# femto.net
KiCad netlist of a schematic drawn in EAGLE
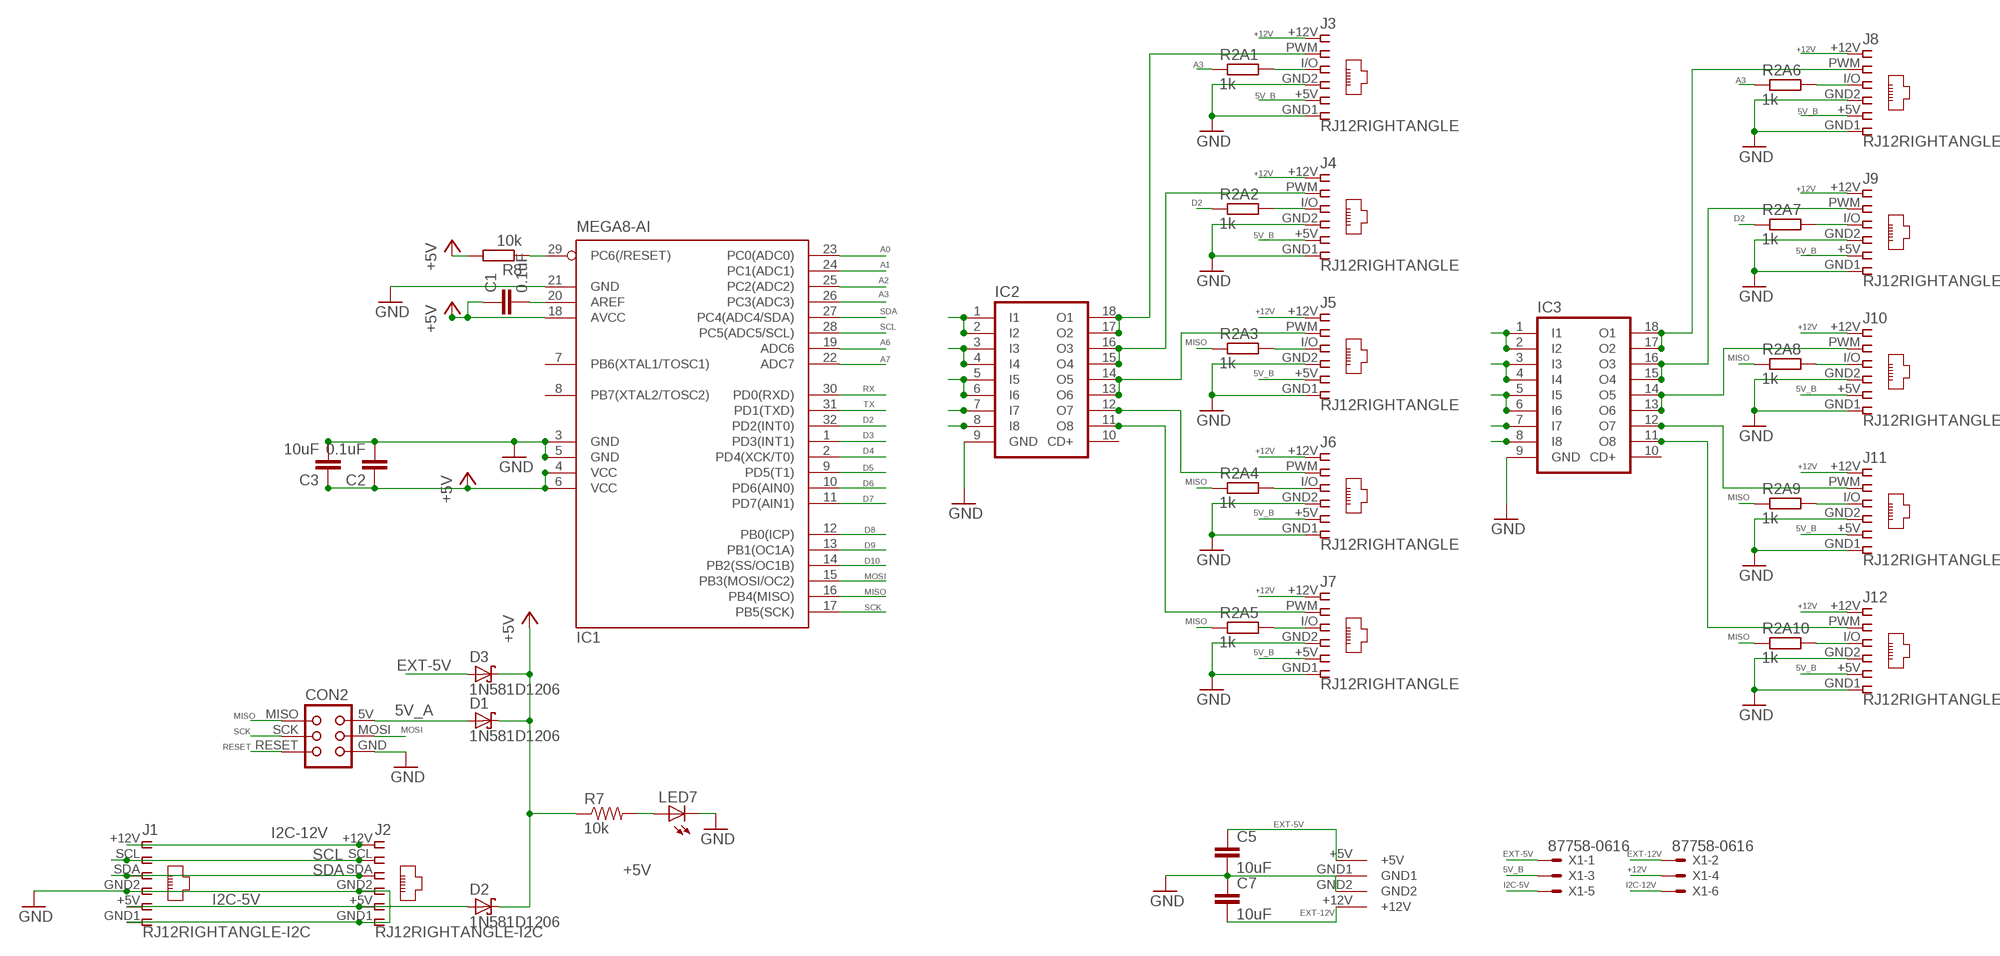
[diagram p0: schematic, sheet 1]

(export (version "E")
  (design (tool "Eeschema 10.0.6"))
  (components
    (comp (ref "C1")
      (value "0.1uF")
      (footprint "eagle-import:C1206")
      (libsource (lib "eagle-import") (part "resistor_C-EUC1206"))
    )
    (comp (ref "C2")
      (value "0.1uF")
      (footprint "eagle-import:C1206")
      (libsource (lib "eagle-import") (part "resistor_C-EUC1206"))
    )
    (comp (ref "C3")
      (value "10uF")
      (footprint "eagle-import:C1206")
      (libsource (lib "eagle-import") (part "resistor_C-EUC1206"))
    )
    (comp (ref "C5")
      (value "10uF")
      (footprint "eagle-import:C1206")
      (libsource (lib "eagle-import") (part "C-EUC1206"))
    )
    (comp (ref "C7")
      (value "10uF")
      (footprint "eagle-import:C1206")
      (libsource (lib "eagle-import") (part "C-EUC1206"))
    )
    (comp (ref "CON2")
      (value "TINYISPTAG")
      (footprint "eagle-import:TC2030-MCP")
      (libsource (lib "eagle-import") (part "TINYISPTAG"))
    )
    (comp (ref "D1")
      (value "1N581D1206")
      (footprint "eagle-import:LED-1206")
      (libsource (lib "eagle-import") (part "1N581D1206"))
    )
    (comp (ref "D2")
      (value "1N581D1206")
      (footprint "eagle-import:LED-1206")
      (libsource (lib "eagle-import") (part "1N581D1206"))
    )
    (comp (ref "D3")
      (value "1N581D1206")
      (footprint "eagle-import:LED-1206")
      (libsource (lib "eagle-import") (part "1N581D1206"))
    )
    (comp (ref "IC1")
      (value "MEGA8-AI")
      (footprint "eagle-import:TQFP32-08")
      (fields (field (name "MPN") "ATMEGA8-16AU"))
      (libsource (lib "eagle-import") (part "MEGA8-AI"))
    )
    (comp (ref "IC2")
      (value "ULN2803A")
      (footprint "eagle-import:SO18W")
      (libsource (lib "eagle-import") (part "ULN2803A"))
    )
    (comp (ref "IC3")
      (value "ULN2803A")
      (footprint "eagle-import:SO18W")
      (libsource (lib "eagle-import") (part "ULN2803A"))
    )
    (comp (ref "J1")
      (value "RJ12RIGHTANGLE-I2C")
      (footprint "eagle-import:RJ12-RIGHTANGLE-I2C")
      (libsource (lib "eagle-import") (part "RJ12RIGHTANGLE-I2C"))
    )
    (comp (ref "J2")
      (value "RJ12RIGHTANGLE-I2C")
      (footprint "eagle-import:RJ12-RIGHTANGLE-I2C")
      (libsource (lib "eagle-import") (part "RJ12RIGHTANGLE-I2C"))
    )
    (comp (ref "J3")
      (value "RJ12RIGHTANGLE")
      (footprint "eagle-import:RJ12-RIGHTANGLE")
      (libsource (lib "eagle-import") (part "RJ12RIGHTANGLE"))
    )
    (comp (ref "J4")
      (value "RJ12RIGHTANGLE")
      (footprint "eagle-import:RJ12-RIGHTANGLE")
      (libsource (lib "eagle-import") (part "RJ12RIGHTANGLE"))
    )
    (comp (ref "J5")
      (value "RJ12RIGHTANGLE")
      (footprint "eagle-import:RJ12-RIGHTANGLE")
      (libsource (lib "eagle-import") (part "RJ12RIGHTANGLE"))
    )
    (comp (ref "J6")
      (value "RJ12RIGHTANGLE")
      (footprint "eagle-import:RJ12-RIGHTANGLE")
      (libsource (lib "eagle-import") (part "RJ12RIGHTANGLE"))
    )
    (comp (ref "J7")
      (value "RJ12RIGHTANGLE")
      (footprint "eagle-import:RJ12-RIGHTANGLE")
      (libsource (lib "eagle-import") (part "RJ12RIGHTANGLE"))
    )
    (comp (ref "J8")
      (value "RJ12RIGHTANGLE")
      (footprint "eagle-import:RJ12-RIGHTANGLE")
      (libsource (lib "eagle-import") (part "RJ12RIGHTANGLE"))
    )
    (comp (ref "J9")
      (value "RJ12RIGHTANGLE")
      (footprint "eagle-import:RJ12-RIGHTANGLE")
      (libsource (lib "eagle-import") (part "RJ12RIGHTANGLE"))
    )
    (comp (ref "J10")
      (value "RJ12RIGHTANGLE")
      (footprint "eagle-import:RJ12-RIGHTANGLE")
      (libsource (lib "eagle-import") (part "RJ12RIGHTANGLE"))
    )
    (comp (ref "J11")
      (value "RJ12RIGHTANGLE")
      (footprint "eagle-import:RJ12-RIGHTANGLE")
      (libsource (lib "eagle-import") (part "RJ12RIGHTANGLE"))
    )
    (comp (ref "J12")
      (value "RJ12RIGHTANGLE")
      (footprint "eagle-import:RJ12-RIGHTANGLE")
      (libsource (lib "eagle-import") (part "RJ12RIGHTANGLE"))
    )
    (comp (ref "LED7")
      (value "LEDCHIP-LED0603")
      (footprint "eagle-import:CHIP-LED0603")
      (libsource (lib "eagle-import") (part "LEDCHIP-LED0603"))
    )
    (comp (ref "R2A1")
      (value "1k")
      (footprint "eagle-import:M1206")
      (libsource (lib "eagle-import") (part "R-EU_M1206"))
    )
    (comp (ref "R2A2")
      (value "1k")
      (footprint "eagle-import:M1206")
      (libsource (lib "eagle-import") (part "R-EU_M1206"))
    )
    (comp (ref "R2A3")
      (value "1k")
      (footprint "eagle-import:M1206")
      (libsource (lib "eagle-import") (part "R-EU_M1206"))
    )
    (comp (ref "R2A4")
      (value "1k")
      (footprint "eagle-import:M1206")
      (libsource (lib "eagle-import") (part "R-EU_M1206"))
    )
    (comp (ref "R2A5")
      (value "1k")
      (footprint "eagle-import:M1206")
      (libsource (lib "eagle-import") (part "R-EU_M1206"))
    )
    (comp (ref "R2A6")
      (value "1k")
      (footprint "eagle-import:M1206")
      (libsource (lib "eagle-import") (part "R-EU_M1206"))
    )
    (comp (ref "R2A7")
      (value "1k")
      (footprint "eagle-import:M1206")
      (libsource (lib "eagle-import") (part "R-EU_M1206"))
    )
    (comp (ref "R2A8")
      (value "1k")
      (footprint "eagle-import:M1206")
      (libsource (lib "eagle-import") (part "R-EU_M1206"))
    )
    (comp (ref "R2A9")
      (value "1k")
      (footprint "eagle-import:M1206")
      (libsource (lib "eagle-import") (part "R-EU_M1206"))
    )
    (comp (ref "R2A10")
      (value "1k")
      (footprint "eagle-import:M1206")
      (libsource (lib "eagle-import") (part "R-EU_M1206"))
    )
    (comp (ref "R7")
      (value "10k")
      (footprint "eagle-import:0603-RES")
      (libsource (lib "eagle-import") (part "RESISTOR0603-RES"))
    )
    (comp (ref "R8")
      (value "10k")
      (footprint "eagle-import:M1206")
      (libsource (lib "eagle-import") (part "R-EU_M1206"))
    )
    (comp (ref "U$1")
      (value "KPJX-4S-S")
      (footprint "eagle-import:KPJX-4S-S")
      (libsource (lib "eagle-import") (part "KPJX-4S-S"))
    )
    (comp (ref "X1")
      (value "87758-0616")
      (footprint "eagle-import:87758-0616")
      (libsource (lib "eagle-import") (part "87758-0616"))
    )
  )
  (nets
    (net (code "1") (name "+5V") (class "Default")
      (node (ref "C1") (pin "1") (pinfunction "1_1") (pintype "passive"))
      (node (ref "C2") (pin "1") (pinfunction "1_1") (pintype "passive"))
      (node (ref "C3") (pin "1") (pinfunction "1_1") (pintype "passive"))
      (node (ref "D1") (pin "C") (pinfunction "C_C") (pintype "passive"))
      (node (ref "D2") (pin "C") (pinfunction "C_C") (pintype "passive"))
      (node (ref "D3") (pin "C") (pinfunction "C_C") (pintype "passive"))
      (node (ref "IC1") (pin "18") (pinfunction "AVCC_18") (pintype "power_in"))
      (node (ref "IC1") (pin "4") (pinfunction "VCC_4") (pintype "power_in"))
      (node (ref "IC1") (pin "6") (pinfunction "VCC_6") (pintype "power_in"))
      (node (ref "R7") (pin "1") (pinfunction "1_1") (pintype "passive"))
      (node (ref "R8") (pin "2") (pinfunction "2_2") (pintype "passive"))
    )
    (net (code "2") (name "/+12V") (class "Default")
      (node (ref "J10") (pin "+12V") (pinfunction "1_+12V") (pintype "bidirectional"))
      (node (ref "J11") (pin "+12V") (pinfunction "1_+12V") (pintype "bidirectional"))
      (node (ref "J12") (pin "+12V") (pinfunction "1_+12V") (pintype "bidirectional"))
      (node (ref "J3") (pin "+12V") (pinfunction "1_+12V") (pintype "bidirectional"))
      (node (ref "J4") (pin "+12V") (pinfunction "1_+12V") (pintype "bidirectional"))
      (node (ref "J5") (pin "+12V") (pinfunction "1_+12V") (pintype "bidirectional"))
      (node (ref "J6") (pin "+12V") (pinfunction "1_+12V") (pintype "bidirectional"))
      (node (ref "J7") (pin "+12V") (pinfunction "1_+12V") (pintype "bidirectional"))
      (node (ref "J8") (pin "+12V") (pinfunction "1_+12V") (pintype "bidirectional"))
      (node (ref "J9") (pin "+12V") (pinfunction "1_+12V") (pintype "bidirectional"))
      (node (ref "X1") (pin "4") (pinfunction "S_4") (pintype "passive"))
    )
    (net (code "3") (name "/5V_A") (class "Default")
      (node (ref "CON2") (pin "5V") (pinfunction "VCC_5V") (pintype "passive"))
      (node (ref "D1") (pin "A") (pinfunction "A_A") (pintype "passive"))
    )
    (net (code "4") (name "/5V_B") (class "Default")
      (node (ref "J10") (pin "+5V") (pinfunction "5_+5V") (pintype "bidirectional"))
      (node (ref "J11") (pin "+5V") (pinfunction "5_+5V") (pintype "bidirectional"))
      (node (ref "J12") (pin "+5V") (pinfunction "5_+5V") (pintype "bidirectional"))
      (node (ref "J3") (pin "+5V") (pinfunction "5_+5V") (pintype "bidirectional"))
      (node (ref "J4") (pin "+5V") (pinfunction "5_+5V") (pintype "bidirectional"))
      (node (ref "J5") (pin "+5V") (pinfunction "5_+5V") (pintype "bidirectional"))
      (node (ref "J6") (pin "+5V") (pinfunction "5_+5V") (pintype "bidirectional"))
      (node (ref "J7") (pin "+5V") (pinfunction "5_+5V") (pintype "bidirectional"))
      (node (ref "J8") (pin "+5V") (pinfunction "5_+5V") (pintype "bidirectional"))
      (node (ref "J9") (pin "+5V") (pinfunction "5_+5V") (pintype "bidirectional"))
      (node (ref "X1") (pin "3") (pinfunction "S_3") (pintype "passive"))
    )
    (net (code "5") (name "/A0") (class "Default")
      (node (ref "IC1") (pin "23") (pinfunction "PC0(ADC0)_23") (pintype "bidirectional"))
    )
    (net (code "6") (name "/A1") (class "Default")
      (node (ref "IC1") (pin "24") (pinfunction "PC1(ADC1)_24") (pintype "bidirectional"))
    )
    (net (code "7") (name "/A2") (class "Default")
      (node (ref "IC1") (pin "25") (pinfunction "PC2(ADC2)_25") (pintype "bidirectional"))
    )
    (net (code "8") (name "/A3") (class "Default")
      (node (ref "IC1") (pin "26") (pinfunction "PC3(ADC3)_26") (pintype "bidirectional"))
      (node (ref "R2A1") (pin "1") (pinfunction "1_1") (pintype "passive"))
      (node (ref "R2A6") (pin "1") (pinfunction "1_1") (pintype "passive"))
    )
    (net (code "9") (name "/A6") (class "Default")
      (node (ref "IC1") (pin "19") (pinfunction "ADC6_19") (pintype "bidirectional"))
    )
    (net (code "10") (name "/A7") (class "Default")
      (node (ref "IC1") (pin "22") (pinfunction "ADC7_22") (pintype "bidirectional"))
    )
    (net (code "11") (name "/D2") (class "Default")
      (node (ref "IC1") (pin "32") (pinfunction "PD2(INT0)_32") (pintype "bidirectional"))
      (node (ref "R2A2") (pin "1") (pinfunction "1_1") (pintype "passive"))
      (node (ref "R2A7") (pin "1") (pinfunction "1_1") (pintype "passive"))
    )
    (net (code "12") (name "/D3") (class "Default")
      (node (ref "IC1") (pin "1") (pinfunction "PD3(INT1)_1") (pintype "bidirectional"))
    )
    (net (code "13") (name "/D4") (class "Default")
      (node (ref "IC1") (pin "2") (pinfunction "PD4(XCK/T0)_2") (pintype "bidirectional"))
    )
    (net (code "14") (name "/D5") (class "Default")
      (node (ref "IC1") (pin "9") (pinfunction "PD5(T1)_9") (pintype "bidirectional"))
    )
    (net (code "15") (name "/D6") (class "Default")
      (node (ref "IC1") (pin "10") (pinfunction "PD6(AIN0)_10") (pintype "bidirectional"))
    )
    (net (code "16") (name "/D7") (class "Default")
      (node (ref "IC1") (pin "11") (pinfunction "PD7(AIN1)_11") (pintype "bidirectional"))
    )
    (net (code "17") (name "/D8") (class "Default")
      (node (ref "IC1") (pin "12") (pinfunction "PB0(ICP)_12") (pintype "bidirectional"))
    )
    (net (code "18") (name "/D9") (class "Default")
      (node (ref "IC1") (pin "13") (pinfunction "PB1(OC1A)_13") (pintype "bidirectional"))
    )
    (net (code "19") (name "/D10") (class "Default")
      (node (ref "IC1") (pin "14") (pinfunction "PB2(SS/OC1B)_14") (pintype "bidirectional"))
    )
    (net (code "20") (name "/EXT-5V") (class "Default")
      (node (ref "C5") (pin "1") (pinfunction "1_1") (pintype "passive"))
      (node (ref "D3") (pin "A") (pinfunction "A_A") (pintype "passive"))
      (node (ref "U$1") (pin "+5V") (pinfunction "+5V_+5V") (pintype "power_in"))
      (node (ref "X1") (pin "1") (pinfunction "S_1") (pintype "passive"))
    )
    (net (code "21") (name "/EXT-12V") (class "Default")
      (node (ref "C7") (pin "2") (pinfunction "2_2") (pintype "passive"))
      (node (ref "U$1") (pin "+12V") (pinfunction "+12V_+12V") (pintype "power_in"))
      (node (ref "X1") (pin "2") (pinfunction "S_2") (pintype "passive"))
    )
    (net (code "22") (name "/I2C-5V") (class "Default")
      (node (ref "D2") (pin "A") (pinfunction "A_A") (pintype "passive"))
      (node (ref "J1") (pin "+5V") (pinfunction "5_+5V") (pintype "bidirectional"))
      (node (ref "J2") (pin "+5V") (pinfunction "5_+5V") (pintype "bidirectional"))
      (node (ref "X1") (pin "5") (pinfunction "S_5") (pintype "passive"))
    )
    (net (code "23") (name "/I2C-12V") (class "Default")
      (node (ref "J1") (pin "+12V") (pinfunction "1_+12V") (pintype "bidirectional"))
      (node (ref "J2") (pin "+12V") (pinfunction "1_+12V") (pintype "bidirectional"))
      (node (ref "X1") (pin "6") (pinfunction "S_6") (pintype "passive"))
    )
    (net (code "24") (name "/MISO") (class "Default")
      (node (ref "CON2") (pin "MISO") (pinfunction "MISO_MISO") (pintype "passive"))
      (node (ref "IC1") (pin "16") (pinfunction "PB4(MISO)_16") (pintype "bidirectional"))
      (node (ref "R2A10") (pin "1") (pinfunction "1_1") (pintype "passive"))
      (node (ref "R2A3") (pin "1") (pinfunction "1_1") (pintype "passive"))
      (node (ref "R2A4") (pin "1") (pinfunction "1_1") (pintype "passive"))
      (node (ref "R2A5") (pin "1") (pinfunction "1_1") (pintype "passive"))
      (node (ref "R2A8") (pin "1") (pinfunction "1_1") (pintype "passive"))
      (node (ref "R2A9") (pin "1") (pinfunction "1_1") (pintype "passive"))
    )
    (net (code "25") (name "/MOSI") (class "Default")
      (node (ref "CON2") (pin "MOSI") (pinfunction "MOSI_MOSI") (pintype "passive"))
      (node (ref "IC1") (pin "15") (pinfunction "PB3(MOSI/OC2)_15") (pintype "bidirectional"))
    )
    (net (code "26") (name "/RESET") (class "Default")
      (node (ref "CON2") (pin "RESET") (pinfunction "RESET_RESET") (pintype "passive"))
      (node (ref "IC1") (pin "29") (pinfunction "PC6(/RESET)_29") (pintype "bidirectional"))
      (node (ref "R8") (pin "1") (pinfunction "1_1") (pintype "passive"))
    )
    (net (code "27") (name "/RX") (class "Default")
      (node (ref "IC1") (pin "30") (pinfunction "PD0(RXD)_30") (pintype "bidirectional"))
    )
    (net (code "28") (name "/SCK") (class "Default")
      (node (ref "CON2") (pin "SCK") (pinfunction "SCK_SCK") (pintype "passive"))
      (node (ref "IC1") (pin "17") (pinfunction "PB5(SCK)_17") (pintype "bidirectional"))
    )
    (net (code "29") (name "/SCL") (class "Default")
      (node (ref "IC1") (pin "28") (pinfunction "PC5(ADC5/SCL)_28") (pintype "bidirectional"))
      (node (ref "J1") (pin "SCL") (pinfunction "2_SCL") (pintype "bidirectional"))
      (node (ref "J2") (pin "SCL") (pinfunction "2_SCL") (pintype "bidirectional"))
    )
    (net (code "30") (name "/SDA") (class "Default")
      (node (ref "IC1") (pin "27") (pinfunction "PC4(ADC4/SDA)_27") (pintype "bidirectional"))
      (node (ref "J1") (pin "SDA") (pinfunction "3_SDA") (pintype "bidirectional"))
      (node (ref "J2") (pin "SDA") (pinfunction "3_SDA") (pintype "bidirectional"))
    )
    (net (code "31") (name "/TX") (class "Default")
      (node (ref "IC1") (pin "31") (pinfunction "PD1(TXD)_31") (pintype "bidirectional"))
    )
    (net (code "32") (name "GND") (class "Default")
      (node (ref "C2") (pin "2") (pinfunction "2_2") (pintype "passive"))
      (node (ref "C3") (pin "2") (pinfunction "2_2") (pintype "passive"))
      (node (ref "C5") (pin "2") (pinfunction "2_2") (pintype "passive"))
      (node (ref "C7") (pin "1") (pinfunction "1_1") (pintype "passive"))
      (node (ref "CON2") (pin "GND") (pinfunction "GND_GND") (pintype "passive"))
      (node (ref "IC1") (pin "21") (pinfunction "GND_21") (pintype "power_in"))
      (node (ref "IC1") (pin "3") (pinfunction "GND_3") (pintype "power_in"))
      (node (ref "IC1") (pin "5") (pinfunction "GND_5") (pintype "power_in"))
      (node (ref "IC2") (pin "9") (pinfunction "GND_9") (pintype "power_in"))
      (node (ref "IC3") (pin "9") (pinfunction "GND_9") (pintype "power_in"))
      (node (ref "J1") (pin "GND1") (pinfunction "6_GND1") (pintype "bidirectional"))
      (node (ref "J1") (pin "GND2") (pinfunction "4_GND2") (pintype "bidirectional"))
      (node (ref "J10") (pin "GND1") (pinfunction "6_GND1") (pintype "bidirectional"))
      (node (ref "J10") (pin "GND2") (pinfunction "4_GND2") (pintype "bidirectional"))
      (node (ref "J11") (pin "GND1") (pinfunction "6_GND1") (pintype "bidirectional"))
      (node (ref "J11") (pin "GND2") (pinfunction "4_GND2") (pintype "bidirectional"))
      (node (ref "J12") (pin "GND1") (pinfunction "6_GND1") (pintype "bidirectional"))
      (node (ref "J12") (pin "GND2") (pinfunction "4_GND2") (pintype "bidirectional"))
      (node (ref "J2") (pin "GND1") (pinfunction "6_GND1") (pintype "bidirectional"))
      (node (ref "J2") (pin "GND2") (pinfunction "4_GND2") (pintype "bidirectional"))
      (node (ref "J3") (pin "GND1") (pinfunction "6_GND1") (pintype "bidirectional"))
      (node (ref "J3") (pin "GND2") (pinfunction "4_GND2") (pintype "bidirectional"))
      (node (ref "J4") (pin "GND1") (pinfunction "6_GND1") (pintype "bidirectional"))
      (node (ref "J4") (pin "GND2") (pinfunction "4_GND2") (pintype "bidirectional"))
      (node (ref "J5") (pin "GND1") (pinfunction "6_GND1") (pintype "bidirectional"))
      (node (ref "J5") (pin "GND2") (pinfunction "4_GND2") (pintype "bidirectional"))
      (node (ref "J6") (pin "GND1") (pinfunction "6_GND1") (pintype "bidirectional"))
      (node (ref "J6") (pin "GND2") (pinfunction "4_GND2") (pintype "bidirectional"))
      (node (ref "J7") (pin "GND1") (pinfunction "6_GND1") (pintype "bidirectional"))
      (node (ref "J7") (pin "GND2") (pinfunction "4_GND2") (pintype "bidirectional"))
      (node (ref "J8") (pin "GND1") (pinfunction "6_GND1") (pintype "bidirectional"))
      (node (ref "J8") (pin "GND2") (pinfunction "4_GND2") (pintype "bidirectional"))
      (node (ref "J9") (pin "GND1") (pinfunction "6_GND1") (pintype "bidirectional"))
      (node (ref "J9") (pin "GND2") (pinfunction "4_GND2") (pintype "bidirectional"))
      (node (ref "LED7") (pin "C") (pinfunction "C_C") (pintype "passive"))
      (node (ref "U$1") (pin "GND1") (pinfunction "GND1_GND1") (pintype "input"))
      (node (ref "U$1") (pin "GND2") (pinfunction "GND2_GND2") (pintype "input"))
    )
    (net (code "33") (name "Net-(IC1-AREF)") (class "Default")
      (node (ref "C1") (pin "2") (pinfunction "2_2") (pintype "passive"))
      (node (ref "IC1") (pin "20") (pinfunction "AREF_20") (pintype "passive"))
    )
    (net (code "34") (name "Net-(IC2-I1)") (class "Default")
      (node (ref "IC2") (pin "1") (pinfunction "I1_1") (pintype "input"))
      (node (ref "IC2") (pin "2") (pinfunction "I2_2") (pintype "input"))
    )
    (net (code "35") (name "Net-(IC2-I3)") (class "Default")
      (node (ref "IC2") (pin "3") (pinfunction "I3_3") (pintype "input"))
      (node (ref "IC2") (pin "4") (pinfunction "I4_4") (pintype "input"))
    )
    (net (code "36") (name "Net-(IC2-I5)") (class "Default")
      (node (ref "IC2") (pin "5") (pinfunction "I5_5") (pintype "input"))
      (node (ref "IC2") (pin "6") (pinfunction "I6_6") (pintype "input"))
    )
    (net (code "37") (name "Net-(IC2-O1)") (class "Default")
      (node (ref "IC2") (pin "17") (pinfunction "O2_17") (pintype "open_collector"))
      (node (ref "IC2") (pin "18") (pinfunction "O1_18") (pintype "open_collector"))
      (node (ref "J3") (pin "PWM") (pinfunction "2_PWM") (pintype "bidirectional"))
    )
    (net (code "38") (name "Net-(IC2-O3)") (class "Default")
      (node (ref "IC2") (pin "15") (pinfunction "O4_15") (pintype "open_collector"))
      (node (ref "IC2") (pin "16") (pinfunction "O3_16") (pintype "open_collector"))
      (node (ref "J4") (pin "PWM") (pinfunction "2_PWM") (pintype "bidirectional"))
    )
    (net (code "39") (name "Net-(IC2-O5)") (class "Default")
      (node (ref "IC2") (pin "13") (pinfunction "O6_13") (pintype "open_collector"))
      (node (ref "IC2") (pin "14") (pinfunction "O5_14") (pintype "open_collector"))
      (node (ref "J5") (pin "PWM") (pinfunction "2_PWM") (pintype "bidirectional"))
    )
    (net (code "40") (name "Net-(IC2-O7)") (class "Default")
      (node (ref "IC2") (pin "12") (pinfunction "O7_12") (pintype "open_collector"))
      (node (ref "J6") (pin "PWM") (pinfunction "2_PWM") (pintype "bidirectional"))
    )
    (net (code "41") (name "Net-(IC2-O8)") (class "Default")
      (node (ref "IC2") (pin "11") (pinfunction "O8_11") (pintype "open_collector"))
      (node (ref "J7") (pin "PWM") (pinfunction "2_PWM") (pintype "bidirectional"))
    )
    (net (code "42") (name "Net-(IC3-I1)") (class "Default")
      (node (ref "IC3") (pin "1") (pinfunction "I1_1") (pintype "input"))
      (node (ref "IC3") (pin "2") (pinfunction "I2_2") (pintype "input"))
    )
    (net (code "43") (name "Net-(IC3-I3)") (class "Default")
      (node (ref "IC3") (pin "3") (pinfunction "I3_3") (pintype "input"))
      (node (ref "IC3") (pin "4") (pinfunction "I4_4") (pintype "input"))
    )
    (net (code "44") (name "Net-(IC3-I5)") (class "Default")
      (node (ref "IC3") (pin "5") (pinfunction "I5_5") (pintype "input"))
      (node (ref "IC3") (pin "6") (pinfunction "I6_6") (pintype "input"))
    )
    (net (code "45") (name "Net-(IC3-O1)") (class "Default")
      (node (ref "IC3") (pin "17") (pinfunction "O2_17") (pintype "open_collector"))
      (node (ref "IC3") (pin "18") (pinfunction "O1_18") (pintype "open_collector"))
      (node (ref "J8") (pin "PWM") (pinfunction "2_PWM") (pintype "bidirectional"))
    )
    (net (code "46") (name "Net-(IC3-O3)") (class "Default")
      (node (ref "IC3") (pin "15") (pinfunction "O4_15") (pintype "open_collector"))
      (node (ref "IC3") (pin "16") (pinfunction "O3_16") (pintype "open_collector"))
      (node (ref "J9") (pin "PWM") (pinfunction "2_PWM") (pintype "bidirectional"))
    )
    (net (code "47") (name "Net-(IC3-O5)") (class "Default")
      (node (ref "IC3") (pin "13") (pinfunction "O6_13") (pintype "open_collector"))
      (node (ref "IC3") (pin "14") (pinfunction "O5_14") (pintype "open_collector"))
      (node (ref "J10") (pin "PWM") (pinfunction "2_PWM") (pintype "bidirectional"))
    )
    (net (code "48") (name "Net-(IC3-O7)") (class "Default")
      (node (ref "IC3") (pin "12") (pinfunction "O7_12") (pintype "open_collector"))
      (node (ref "J11") (pin "PWM") (pinfunction "2_PWM") (pintype "bidirectional"))
    )
    (net (code "49") (name "Net-(IC3-O8)") (class "Default")
      (node (ref "IC3") (pin "11") (pinfunction "O8_11") (pintype "open_collector"))
      (node (ref "J12") (pin "PWM") (pinfunction "2_PWM") (pintype "bidirectional"))
    )
    (net (code "50") (name "Net-(J3-3)") (class "Default")
      (node (ref "J3") (pin "I/O") (pinfunction "3_I/O") (pintype "bidirectional"))
      (node (ref "R2A1") (pin "2") (pinfunction "2_2") (pintype "passive"))
    )
    (net (code "51") (name "Net-(J4-3)") (class "Default")
      (node (ref "J4") (pin "I/O") (pinfunction "3_I/O") (pintype "bidirectional"))
      (node (ref "R2A2") (pin "2") (pinfunction "2_2") (pintype "passive"))
    )
    (net (code "52") (name "Net-(J5-3)") (class "Default")
      (node (ref "J5") (pin "I/O") (pinfunction "3_I/O") (pintype "bidirectional"))
      (node (ref "R2A3") (pin "2") (pinfunction "2_2") (pintype "passive"))
    )
    (net (code "53") (name "Net-(J6-3)") (class "Default")
      (node (ref "J6") (pin "I/O") (pinfunction "3_I/O") (pintype "bidirectional"))
      (node (ref "R2A4") (pin "2") (pinfunction "2_2") (pintype "passive"))
    )
    (net (code "54") (name "Net-(J7-3)") (class "Default")
      (node (ref "J7") (pin "I/O") (pinfunction "3_I/O") (pintype "bidirectional"))
      (node (ref "R2A5") (pin "2") (pinfunction "2_2") (pintype "passive"))
    )
    (net (code "55") (name "Net-(J8-3)") (class "Default")
      (node (ref "J8") (pin "I/O") (pinfunction "3_I/O") (pintype "bidirectional"))
      (node (ref "R2A6") (pin "2") (pinfunction "2_2") (pintype "passive"))
    )
    (net (code "56") (name "Net-(J9-3)") (class "Default")
      (node (ref "J9") (pin "I/O") (pinfunction "3_I/O") (pintype "bidirectional"))
      (node (ref "R2A7") (pin "2") (pinfunction "2_2") (pintype "passive"))
    )
    (net (code "57") (name "Net-(J10-3)") (class "Default")
      (node (ref "J10") (pin "I/O") (pinfunction "3_I/O") (pintype "bidirectional"))
      (node (ref "R2A8") (pin "2") (pinfunction "2_2") (pintype "passive"))
    )
    (net (code "58") (name "Net-(J11-3)") (class "Default")
      (node (ref "J11") (pin "I/O") (pinfunction "3_I/O") (pintype "bidirectional"))
      (node (ref "R2A9") (pin "2") (pinfunction "2_2") (pintype "passive"))
    )
    (net (code "59") (name "Net-(J12-3)") (class "Default")
      (node (ref "J12") (pin "I/O") (pinfunction "3_I/O") (pintype "bidirectional"))
      (node (ref "R2A10") (pin "2") (pinfunction "2_2") (pintype "passive"))
    )
    (net (code "60") (name "Net-(LED7-PadA)") (class "Default")
      (node (ref "LED7") (pin "A") (pinfunction "A_A") (pintype "passive"))
      (node (ref "R7") (pin "2") (pinfunction "2_2") (pintype "passive"))
    )
    (net (code "61") (name "unconnected-(IC1-PB6(XTAL1{slash}TOSC1)-Pad7)") (class "Default")
      (node (ref "IC1") (pin "7") (pinfunction "PB6(XTAL1/TOSC1)_7") (pintype "bidirectional"))
    )
    (net (code "62") (name "unconnected-(IC1-PB7(XTAL2{slash}TOSC2)-Pad8)") (class "Default")
      (node (ref "IC1") (pin "8") (pinfunction "PB7(XTAL2/TOSC2)_8") (pintype "bidirectional"))
    )
    (net (code "63") (name "unconnected-(IC2-CD+-Pad10)") (class "Default")
      (node (ref "IC2") (pin "10") (pinfunction "CD+_10") (pintype "passive"))
    )
    (net (code "64") (name "unconnected-(IC2-I7-Pad7)") (class "Default")
      (node (ref "IC2") (pin "7") (pinfunction "I7_7") (pintype "input"))
    )
    (net (code "65") (name "unconnected-(IC2-I8-Pad8)") (class "Default")
      (node (ref "IC2") (pin "8") (pinfunction "I8_8") (pintype "input"))
    )
    (net (code "66") (name "unconnected-(IC3-CD+-Pad10)") (class "Default")
      (node (ref "IC3") (pin "10") (pinfunction "CD+_10") (pintype "passive"))
    )
    (net (code "67") (name "unconnected-(IC3-I7-Pad7)") (class "Default")
      (node (ref "IC3") (pin "7") (pinfunction "I7_7") (pintype "input"))
    )
    (net (code "68") (name "unconnected-(IC3-I8-Pad8)") (class "Default")
      (node (ref "IC3") (pin "8") (pinfunction "I8_8") (pintype "input"))
    )
  )
)
